# 5V-3V3_Divider.net
KiCad netlist of a schematic drawn in Altium Designer
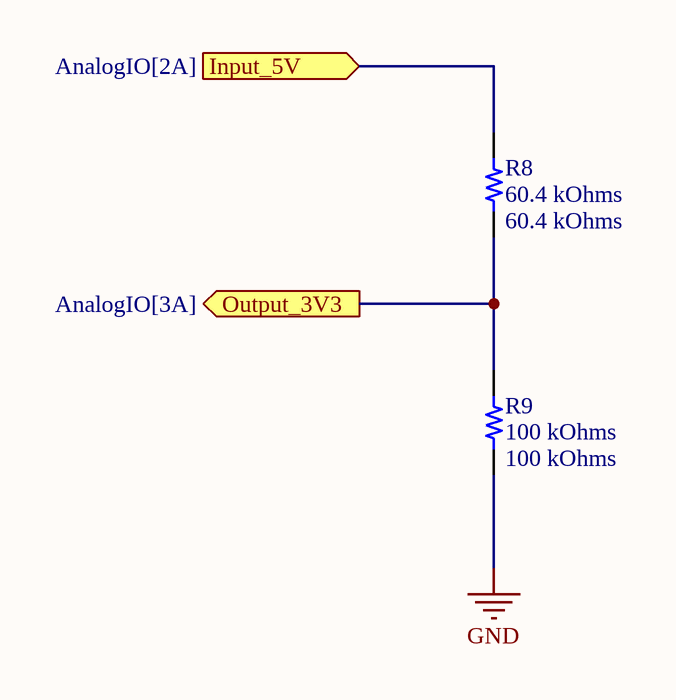
[diagram p0: 5V-3V3_Divider.SchDoc]

(export (version "E")
  (design (tool "Eeschema 10.0.6"))
  (components
    (comp (ref "R8")
      (value "60.4 kOhms")
      (footprint "RES 0603_1608")
      (description "RES SMD 60.4K OHM 1% 1/10W 0603")
      (fields (field (name "PART NUMBER") "AC0603FR-0760K4L") (field (name "ALTIUM_VALUE") "60.4 kOhms"))
      (libsource (lib "altium_library") (part "Resistor"))
    )
    (comp (ref "R9")
      (value "100 kOhms")
      (footprint "RES 0603_1608")
      (description "RES SMD 100K OHM 1% 1/10W 0603")
      (fields (field (name "PART NUMBER") "AA0603FR-07100KL") (field (name "ALTIUM_VALUE") "100 kOhms"))
      (libsource (lib "altium_library") (part "Resistor"))
    )
  )
  (nets
    (net (code "1") (name "/Input_5V") (class "Default")
      (node (ref "R8") (pin "2") (pinfunction "2_2") (pintype "passive"))
    )
    (net (code "2") (name "/Output_3V3") (class "Default")
      (node (ref "R8") (pin "1") (pinfunction "1_1") (pintype "passive"))
      (node (ref "R9") (pin "2") (pinfunction "2_2") (pintype "passive"))
    )
    (net (code "3") (name "GND") (class "Default")
      (node (ref "R9") (pin "1") (pinfunction "1_1") (pintype "passive"))
    )
  )
)
